# relay.net
KiCad netlist of a schematic drawn in Altium Designer
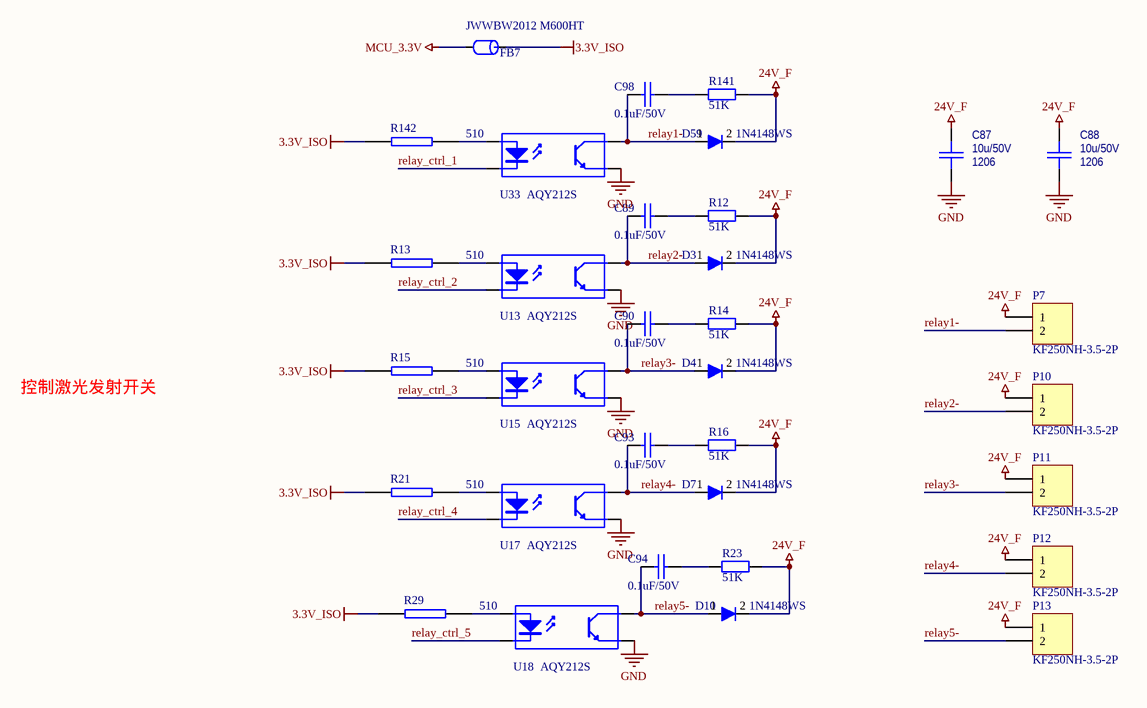
[diagram p0: relay.SchDoc]

(export (version "E")
  (design (tool "Eeschema 10.0.6"))
  (components
    (comp (ref "C87")
      (value "10u/50V")
      (footprint "CAPC3216X156N_1206")
      (fields
        (field (name "TOLERANCE") "[tol]")
        (field (name "PACKAGE") "1206")
        (field (name "PARTNUMBER") "CL31A106KBHNNNE")
      )
      (libsource (lib "Karl") (part "Capacitor_1206"))
    )
    (comp (ref "C88")
      (value "10u/50V")
      (footprint "CAPC3216X156N_1206")
      (fields
        (field (name "TOLERANCE") "[tol]")
        (field (name "PACKAGE") "1206")
        (field (name "PARTNUMBER") "CL31A106KBHNNNE")
      )
      (libsource (lib "Karl") (part "Capacitor_1206"))
    )
    (comp (ref "C89")
      (value "0.1uF/50V")
      (footprint "CAPC1608X092N_0603")
      (fields (field (name "PARTNUMBER") "CC0603KRX7R9BB104"))
      (libsource (lib "*") (part "CAP"))
    )
    (comp (ref "C90")
      (value "0.1uF/50V")
      (footprint "CAPC1608X092N_0603")
      (fields (field (name "PARTNUMBER") "CC0603KRX7R9BB104"))
      (libsource (lib "*") (part "CAP"))
    )
    (comp (ref "C93")
      (value "0.1uF/50V")
      (footprint "CAPC1608X092N_0603")
      (fields (field (name "PARTNUMBER") "CC0603KRX7R9BB104"))
      (libsource (lib "*") (part "CAP"))
    )
    (comp (ref "C94")
      (value "0.1uF/50V")
      (footprint "CAPC1608X092N_0603")
      (fields (field (name "PARTNUMBER") "CC0603KRX7R9BB104"))
      (libsource (lib "*") (part "CAP"))
    )
    (comp (ref "C98")
      (value "0.1uF/50V")
      (footprint "CAPC1608X092N_0603")
      (fields (field (name "PARTNUMBER") "CC0603KRX7R9BB104"))
      (libsource (lib "*") (part "CAP"))
    )
    (comp (ref "D3") (value "1N4148WS") (footprint "SOD323") (libsource (lib "Device2018") (part "LL4148")))
    (comp (ref "D4") (value "1N4148WS") (footprint "SOD323") (libsource (lib "Device2018") (part "LL4148")))
    (comp (ref "D7") (value "1N4148WS") (footprint "SOD323") (libsource (lib "Device2018") (part "LL4148")))
    (comp (ref "D10") (value "1N4148WS") (footprint "SOD323") (libsource (lib "Device2018") (part "LL4148")))
    (comp (ref "D59") (value "1N4148WS") (footprint "SOD323") (libsource (lib "Device2018") (part "LL4148")))
    (comp (ref "FB7")
      (value "JWWBW2012 M600HT")
      (footprint "0805CZ")
      (fields (field (name "PARTNUMBER") "BLM21PG221SN1D"))
      (libsource (lib "Schlib_20110825") (part "FB"))
    )
    (comp (ref "P7")
      (value "KF250NH-3.5-2P")
      (footprint "KF250NH-3.5-2P")
      (fields (field (name "PUBLISHER") "Altium Limited"))
      (libsource (lib "Miscellaneous Connectors") (part "Header 2"))
    )
    (comp (ref "P10")
      (value "KF250NH-3.5-2P")
      (footprint "KF250NH-3.5-2P")
      (fields (field (name "PUBLISHER") "Altium Limited"))
      (libsource (lib "Miscellaneous Connectors") (part "Header 2"))
    )
    (comp (ref "P11")
      (value "KF250NH-3.5-2P")
      (footprint "KF250NH-3.5-2P")
      (fields (field (name "PUBLISHER") "Altium Limited"))
      (libsource (lib "Miscellaneous Connectors") (part "Header 2"))
    )
    (comp (ref "P12")
      (value "KF250NH-3.5-2P")
      (footprint "KF250NH-3.5-2P")
      (fields (field (name "PUBLISHER") "Altium Limited"))
      (libsource (lib "Miscellaneous Connectors") (part "Header 2"))
    )
    (comp (ref "P13")
      (value "KF250NH-3.5-2P")
      (footprint "KF250NH-3.5-2P")
      (fields (field (name "PUBLISHER") "Altium Limited"))
      (libsource (lib "Miscellaneous Connectors") (part "Header 2"))
    )
    (comp (ref "R12")
      (value "51K")
      (footprint "RESC1608X055N_0603")
      (fields (field (name "PARTNUMBER") "RC0603FR-0751KL"))
      (libsource (lib "MQlibrary") (part "Res0805M"))
    )
    (comp (ref "R13")
      (value "510")
      (footprint "RESC1608X055N_0603")
      (fields (field (name "PARTNUMBER") "RC0603FR-07510RL"))
      (libsource (lib "*") (part "RES2"))
    )
    (comp (ref "R14")
      (value "51K")
      (footprint "RESC1608X055N_0603")
      (fields (field (name "PARTNUMBER") "RC0603FR-0751KL"))
      (libsource (lib "MQlibrary") (part "Res0805M"))
    )
    (comp (ref "R15")
      (value "510")
      (footprint "RESC1608X055N_0603")
      (fields (field (name "PARTNUMBER") "RC0603FR-07510RL"))
      (libsource (lib "*") (part "RES2"))
    )
    (comp (ref "R16")
      (value "51K")
      (footprint "RESC1608X055N_0603")
      (fields (field (name "PARTNUMBER") "RC0603FR-0751KL"))
      (libsource (lib "MQlibrary") (part "Res0805M"))
    )
    (comp (ref "R21")
      (value "510")
      (footprint "RESC1608X055N_0603")
      (fields (field (name "PARTNUMBER") "RC0603FR-07510RL"))
      (libsource (lib "*") (part "RES2"))
    )
    (comp (ref "R23")
      (value "51K")
      (footprint "RESC1608X055N_0603")
      (fields (field (name "PARTNUMBER") "RC0603FR-0751KL"))
      (libsource (lib "MQlibrary") (part "Res0805M"))
    )
    (comp (ref "R29")
      (value "510")
      (footprint "RESC1608X055N_0603")
      (fields (field (name "PARTNUMBER") "RC0603FR-07510RL"))
      (libsource (lib "*") (part "RES2"))
    )
    (comp (ref "R141")
      (value "51K")
      (footprint "RESC1608X055N_0603")
      (fields (field (name "PARTNUMBER") "RC0603FR-0751KL"))
      (libsource (lib "MQlibrary") (part "Res0805M"))
    )
    (comp (ref "R142")
      (value "510")
      (footprint "RESC1608X055N_0603")
      (fields (field (name "PARTNUMBER") "RC0603FR-07510RL"))
      (libsource (lib "*") (part "RES2"))
    )
    (comp (ref "U13")
      (value "AQY212S")
      (footprint "sop4")
      (fields (field (name "PUBLISHER") "Altium Limited"))
      (libsource (lib "Miscellaneous Devices") (part "Optoisolator1"))
    )
    (comp (ref "U15")
      (value "AQY212S")
      (footprint "sop4")
      (fields (field (name "PUBLISHER") "Altium Limited"))
      (libsource (lib "Miscellaneous Devices") (part "Optoisolator1"))
    )
    (comp (ref "U17")
      (value "AQY212S")
      (footprint "sop4")
      (fields (field (name "PUBLISHER") "Altium Limited"))
      (libsource (lib "Miscellaneous Devices") (part "Optoisolator1"))
    )
    (comp (ref "U18")
      (value "AQY212S")
      (footprint "sop4")
      (fields (field (name "PUBLISHER") "Altium Limited"))
      (libsource (lib "Miscellaneous Devices") (part "Optoisolator1"))
    )
    (comp (ref "U33")
      (value "AQY212S")
      (footprint "sop4")
      (fields (field (name "PUBLISHER") "Altium Limited"))
      (libsource (lib "Miscellaneous Devices") (part "Optoisolator1"))
    )
  )
  (nets
    (net (code "1") (name "/relay1-") (class "Default")
      (node (ref "C98") (pin "1") (pinfunction "1_1") (pintype "passive"))
      (node (ref "D59") (pin "1") (pinfunction "K_1") (pintype "passive"))
      (node (ref "P7") (pin "2") (pinfunction "2_2") (pintype "passive"))
      (node (ref "U33") (pin "4") (pinfunction "C_4") (pintype "passive"))
    )
    (net (code "2") (name "/relay2-") (class "Default")
      (node (ref "C89") (pin "1") (pinfunction "1_1") (pintype "passive"))
      (node (ref "D3") (pin "1") (pinfunction "K_1") (pintype "passive"))
      (node (ref "P10") (pin "2") (pinfunction "2_2") (pintype "passive"))
      (node (ref "U13") (pin "4") (pinfunction "C_4") (pintype "passive"))
    )
    (net (code "3") (name "/relay3-") (class "Default")
      (node (ref "C90") (pin "1") (pinfunction "1_1") (pintype "passive"))
      (node (ref "D4") (pin "1") (pinfunction "K_1") (pintype "passive"))
      (node (ref "P11") (pin "2") (pinfunction "2_2") (pintype "passive"))
      (node (ref "U15") (pin "4") (pinfunction "C_4") (pintype "passive"))
    )
    (net (code "4") (name "/relay4-") (class "Default")
      (node (ref "C93") (pin "1") (pinfunction "1_1") (pintype "passive"))
      (node (ref "D7") (pin "1") (pinfunction "K_1") (pintype "passive"))
      (node (ref "P12") (pin "2") (pinfunction "2_2") (pintype "passive"))
      (node (ref "U17") (pin "4") (pinfunction "C_4") (pintype "passive"))
    )
    (net (code "5") (name "/relay5-") (class "Default")
      (node (ref "C94") (pin "1") (pinfunction "1_1") (pintype "passive"))
      (node (ref "D10") (pin "1") (pinfunction "K_1") (pintype "passive"))
      (node (ref "P13") (pin "2") (pinfunction "2_2") (pintype "passive"))
      (node (ref "U18") (pin "4") (pinfunction "C_4") (pintype "passive"))
    )
    (net (code "6") (name "/relay_ctrl_1") (class "Default")
      (node (ref "U33") (pin "2") (pinfunction "K_2") (pintype "passive"))
    )
    (net (code "7") (name "/relay_ctrl_2") (class "Default")
      (node (ref "U13") (pin "2") (pinfunction "K_2") (pintype "passive"))
    )
    (net (code "8") (name "/relay_ctrl_3") (class "Default")
      (node (ref "U15") (pin "2") (pinfunction "K_2") (pintype "passive"))
    )
    (net (code "9") (name "/relay_ctrl_4") (class "Default")
      (node (ref "U17") (pin "2") (pinfunction "K_2") (pintype "passive"))
    )
    (net (code "10") (name "/relay_ctrl_5") (class "Default")
      (node (ref "U18") (pin "2") (pinfunction "K_2") (pintype "passive"))
    )
    (net (code "11") (name "3.3V_ISO") (class "Default")
      (node (ref "FB7") (pin "1") (pintype "passive"))
      (node (ref "R13") (pin "2") (pinfunction "2_2") (pintype "passive"))
      (node (ref "R142") (pin "2") (pinfunction "2_2") (pintype "passive"))
      (node (ref "R15") (pin "2") (pinfunction "2_2") (pintype "passive"))
      (node (ref "R21") (pin "2") (pinfunction "2_2") (pintype "passive"))
      (node (ref "R29") (pin "2") (pinfunction "2_2") (pintype "passive"))
    )
    (net (code "12") (name "24V_F") (class "Default")
      (node (ref "C87") (pin "1") (pinfunction "1_1") (pintype "passive"))
      (node (ref "C88") (pin "1") (pinfunction "1_1") (pintype "passive"))
      (node (ref "D10") (pin "2") (pinfunction "A_2") (pintype "passive"))
      (node (ref "D3") (pin "2") (pinfunction "A_2") (pintype "passive"))
      (node (ref "D4") (pin "2") (pinfunction "A_2") (pintype "passive"))
      (node (ref "D59") (pin "2") (pinfunction "A_2") (pintype "passive"))
      (node (ref "D7") (pin "2") (pinfunction "A_2") (pintype "passive"))
      (node (ref "P10") (pin "1") (pinfunction "1_1") (pintype "passive"))
      (node (ref "P11") (pin "1") (pinfunction "1_1") (pintype "passive"))
      (node (ref "P12") (pin "1") (pinfunction "1_1") (pintype "passive"))
      (node (ref "P13") (pin "1") (pinfunction "1_1") (pintype "passive"))
      (node (ref "P7") (pin "1") (pinfunction "1_1") (pintype "passive"))
      (node (ref "R12") (pin "2") (pinfunction "2_2") (pintype "passive"))
      (node (ref "R14") (pin "2") (pinfunction "2_2") (pintype "passive"))
      (node (ref "R141") (pin "2") (pinfunction "2_2") (pintype "passive"))
      (node (ref "R16") (pin "2") (pinfunction "2_2") (pintype "passive"))
      (node (ref "R23") (pin "2") (pinfunction "2_2") (pintype "passive"))
    )
    (net (code "13") (name "GND") (class "Default")
      (node (ref "C87") (pin "2") (pinfunction "2_2") (pintype "passive"))
      (node (ref "C88") (pin "2") (pinfunction "2_2") (pintype "passive"))
      (node (ref "U13") (pin "3") (pinfunction "E_3") (pintype "passive"))
      (node (ref "U15") (pin "3") (pinfunction "E_3") (pintype "passive"))
      (node (ref "U17") (pin "3") (pinfunction "E_3") (pintype "passive"))
      (node (ref "U18") (pin "3") (pinfunction "E_3") (pintype "passive"))
      (node (ref "U33") (pin "3") (pinfunction "E_3") (pintype "passive"))
    )
    (net (code "14") (name "MCU_3.3V") (class "Default") (node (ref "FB7") (pin "2") (pintype "passive")))
    (net (code "15") (name "Net-(C89-Pad2)") (class "Default")
      (node (ref "C89") (pin "2") (pinfunction "2_2") (pintype "passive"))
      (node (ref "R12") (pin "1") (pinfunction "1_1") (pintype "passive"))
    )
    (net (code "16") (name "Net-(C90-Pad2)") (class "Default")
      (node (ref "C90") (pin "2") (pinfunction "2_2") (pintype "passive"))
      (node (ref "R14") (pin "1") (pinfunction "1_1") (pintype "passive"))
    )
    (net (code "17") (name "Net-(C93-Pad2)") (class "Default")
      (node (ref "C93") (pin "2") (pinfunction "2_2") (pintype "passive"))
      (node (ref "R16") (pin "1") (pinfunction "1_1") (pintype "passive"))
    )
    (net (code "18") (name "Net-(C94-Pad2)") (class "Default")
      (node (ref "C94") (pin "2") (pinfunction "2_2") (pintype "passive"))
      (node (ref "R23") (pin "1") (pinfunction "1_1") (pintype "passive"))
    )
    (net (code "19") (name "Net-(C98-Pad2)") (class "Default")
      (node (ref "C98") (pin "2") (pinfunction "2_2") (pintype "passive"))
      (node (ref "R141") (pin "1") (pinfunction "1_1") (pintype "passive"))
    )
    (net (code "20") (name "Net-(U13-A)") (class "Default")
      (node (ref "R13") (pin "1") (pinfunction "1_1") (pintype "passive"))
      (node (ref "U13") (pin "1") (pinfunction "A_1") (pintype "passive"))
    )
    (net (code "21") (name "Net-(U15-A)") (class "Default")
      (node (ref "R15") (pin "1") (pinfunction "1_1") (pintype "passive"))
      (node (ref "U15") (pin "1") (pinfunction "A_1") (pintype "passive"))
    )
    (net (code "22") (name "Net-(U17-A)") (class "Default")
      (node (ref "R21") (pin "1") (pinfunction "1_1") (pintype "passive"))
      (node (ref "U17") (pin "1") (pinfunction "A_1") (pintype "passive"))
    )
    (net (code "23") (name "Net-(U18-A)") (class "Default")
      (node (ref "R29") (pin "1") (pinfunction "1_1") (pintype "passive"))
      (node (ref "U18") (pin "1") (pinfunction "A_1") (pintype "passive"))
    )
    (net (code "24") (name "Net-(U33-A)") (class "Default")
      (node (ref "R142") (pin "1") (pinfunction "1_1") (pintype "passive"))
      (node (ref "U33") (pin "1") (pinfunction "A_1") (pintype "passive"))
    )
  )
)
